# ArduinoProMiniShematic.net
KiCad netlist of a schematic drawn in Altium Designer
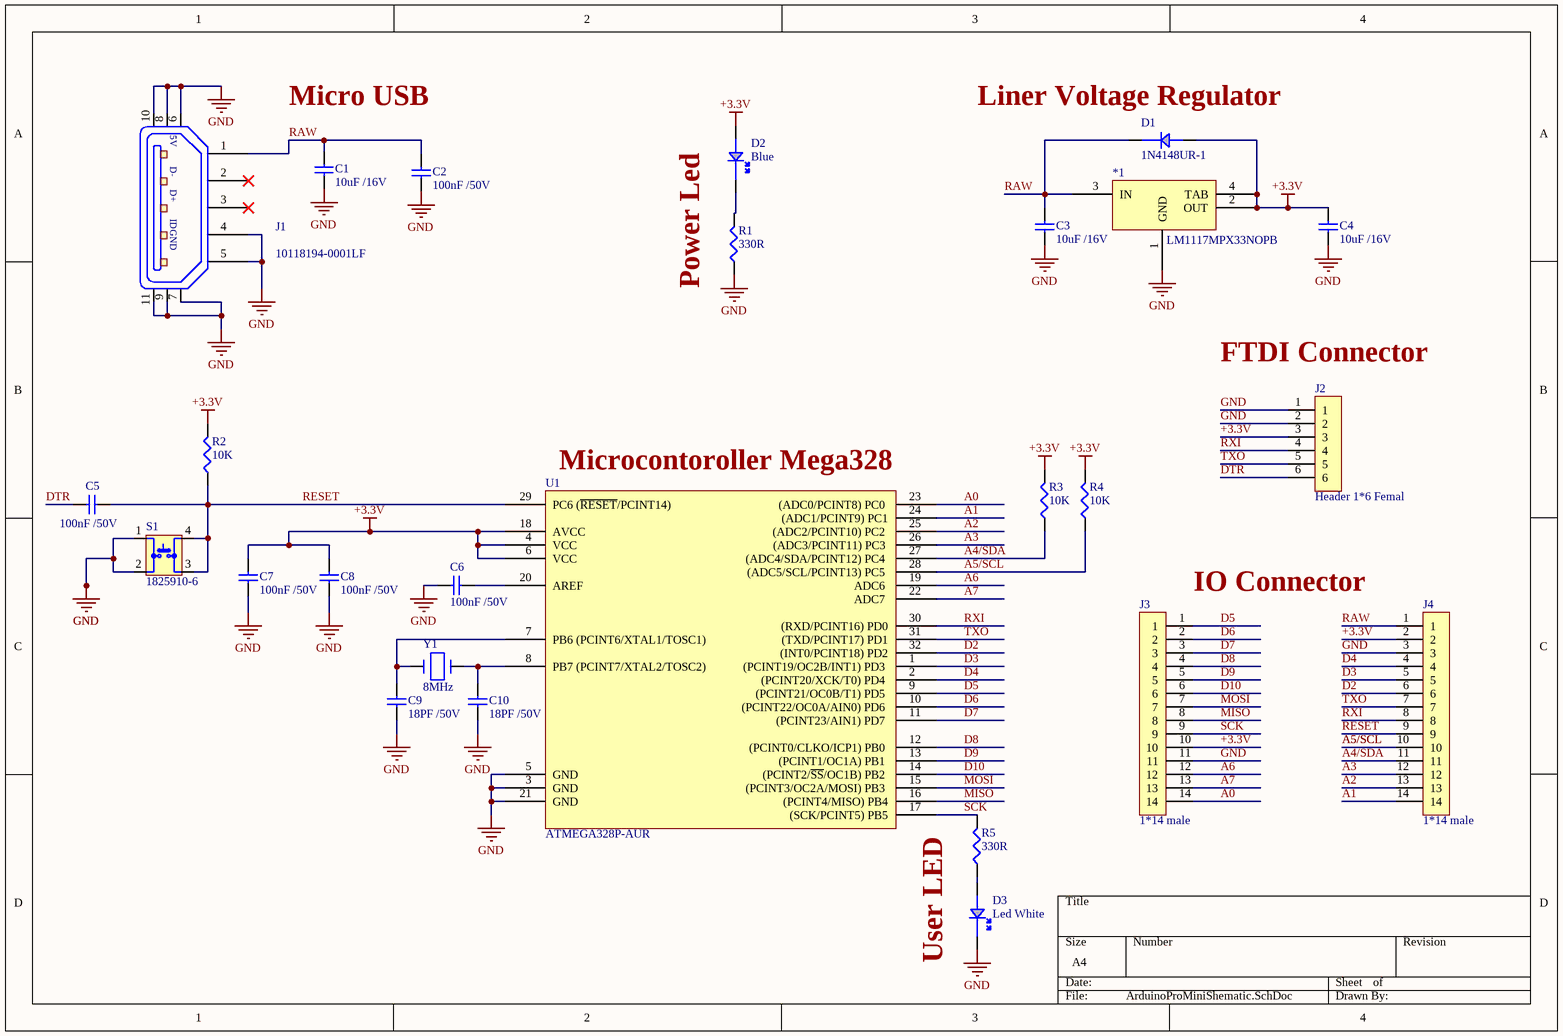
[diagram p0: ArduinoProMiniShematic.SchDoc]

(export (version "E")
  (design (tool "Eeschema 10.0.6"))
  (components
    (comp (ref "*1")
      (value "LM1117MPX33NOPB")
      (footprint "SOT 223")
      (description "IC REG LIN 3.3V 800MA SOT223-4")
      (libsource (lib "ArduinoProMiniSchlib") (part "LM1117MPX33NOPB"))
    )
    (comp (ref "C1")
      (value "10uF /16V")
      (footprint "C 0805")
      (description "KEMET - C0805C106K4PACTU - CERAMIC CAPACITOR, 10UF, 16V, X5R, 10%, 0805")
      (fields (field (name "TOLERANCE") "10%") (field (name "VOLTAGE") "16V"))
      (libsource (lib "ArduinoProMiniSchlib") (part "C0805C106K4PACTU"))
    )
    (comp (ref "C2")
      (value "100nF /50V")
      (footprint "C 0805")
      (description "KEMET         C0805C104Z5VACTU.             CERAMIC CAPACITOR, 0.1UF, 50V, Y5V, +80,-20%, 0805")
      (fields (field (name "VOLTAGE") "50V") (field (name "TOLERANCE") "80%"))
      (libsource (lib "ArduinoProMiniSchlib") (part "C0805C104Z5VACTU"))
    )
    (comp (ref "C3")
      (value "10uF /16V")
      (footprint "C 0805")
      (description "KEMET - C0805C106K4PACTU - CERAMIC CAPACITOR, 10UF, 16V, X5R, 10%, 0805")
      (fields (field (name "TOLERANCE") "10%") (field (name "VOLTAGE") "16V"))
      (libsource (lib "ArduinoProMiniSchlib") (part "C0805C106K4PACTU"))
    )
    (comp (ref "C4")
      (value "10uF /16V")
      (footprint "C 0805")
      (description "KEMET - C0805C106K4PACTU - CERAMIC CAPACITOR, 10UF, 16V, X5R, 10%, 0805")
      (fields (field (name "TOLERANCE") "10%") (field (name "VOLTAGE") "16V"))
      (libsource (lib "ArduinoProMiniSchlib") (part "C0805C106K4PACTU"))
    )
    (comp (ref "C5")
      (value "100nF /50V")
      (footprint "C 0805")
      (description "KEMET         C0805C104Z5VACTU.             CERAMIC CAPACITOR, 0.1UF, 50V, Y5V, +80,-20%, 0805")
      (fields (field (name "VOLTAGE") "50V") (field (name "TOLERANCE") "80%"))
      (libsource (lib "ArduinoProMiniSchlib") (part "C0805C104Z5VACTU"))
    )
    (comp (ref "C6")
      (value "100nF /50V")
      (footprint "C 0805")
      (description "KEMET         C0805C104Z5VACTU.             CERAMIC CAPACITOR, 0.1UF, 50V, Y5V, +80,-20%, 0805")
      (fields (field (name "VOLTAGE") "50V") (field (name "TOLERANCE") "80%"))
      (libsource (lib "ArduinoProMiniSchlib") (part "C0805C104Z5VACTU"))
    )
    (comp (ref "C7")
      (value "100nF /50V")
      (footprint "C 0805")
      (description "KEMET         C0805C104Z5VACTU.             CERAMIC CAPACITOR, 0.1UF, 50V, Y5V, +80,-20%, 0805")
      (fields (field (name "VOLTAGE") "50V") (field (name "TOLERANCE") "80%"))
      (libsource (lib "ArduinoProMiniSchlib") (part "C0805C104Z5VACTU"))
    )
    (comp (ref "C8")
      (value "100nF /50V")
      (footprint "C 0805")
      (description "KEMET         C0805C104Z5VACTU.             CERAMIC CAPACITOR, 0.1UF, 50V, Y5V, +80,-20%, 0805")
      (fields (field (name "VOLTAGE") "50V") (field (name "TOLERANCE") "80%"))
      (libsource (lib "ArduinoProMiniSchlib") (part "C0805C104Z5VACTU"))
    )
    (comp (ref "C9")
      (value "18PF /50V")
      (footprint "C 0805")
      (description "Surface Mount Ceramic Multilayer Capacitor 18pF 5% C0G 50V 0805 Paper T/R")
      (fields (field (name "TOLERANCE") "5%"))
      (libsource (lib "ArduinoProMiniSchlib") (part "CC0805JRNPO9BN180"))
    )
    (comp (ref "C10")
      (value "18PF /50V")
      (footprint "C 0805")
      (description "Surface Mount Ceramic Multilayer Capacitor 18pF 5% C0G 50V 0805 Paper T/R")
      (fields (field (name "TOLERANCE") "5%"))
      (libsource (lib "ArduinoProMiniSchlib") (part "CC0805JRNPO9BN180"))
    )
    (comp (ref "D1")
      (value "1N4148UR-1")
      (footprint "DO 213AA")
      (description "Diode Switching 75V 0.2A 2-Pin DO-213AA")
      (libsource (lib "ArduinoProMiniSchlib") (part "1N4148UR-1"))
    )
    (comp (ref "D2")
      (value "Blue")
      (footprint "LED 0603")
      (description "LED BLUE CLEAR SMD")
      (libsource (lib "ArduinoProMiniSchlib") (part "LTST-C194TBKT"))
    )
    (comp (ref "D3")
      (value "Led White")
      (footprint "LED 0603")
      (description "Led White Clear 0603 SMD")
      (libsource (lib "ArduinoProMiniSchlib") (part "IN-S63AT5UW"))
    )
    (comp (ref "J1")
      (value "10118194-0001LF")
      (footprint "10118194-0001LF")
      (description "CONN USB MICRO B RECPT SMT R/A")
      (libsource (lib "ArduinoProMiniSchlib") (part "10118194-0001LF"))
    )
    (comp (ref "J2")
      (value "Header 1*6 Femal")
      (footprint "Header female 1*6")
      (description "06-WAY SIL VERT SOCKET L/FREE")
      (libsource (lib "ArduinoProMiniSchlib") (part "M20-7820646"))
    )
    (comp (ref "J3")
      (value "1*14 male")
      (footprint "1*4 male header")
      (description "14 Position Single Row Straight Gold Flash Header")
      (libsource (lib "ArduinoProMiniSchlib") (part "PH1-14-UA"))
    )
    (comp (ref "J4")
      (value "1*14 male")
      (footprint "1*4 male header")
      (description "14 Position Single Row Straight Gold Flash Header")
      (libsource (lib "") (part "PH1-14-UA_1"))
    )
    (comp (ref "R1")
      (value "330R")
      (footprint "R 0805")
      (description "YAGEO   RC0805JR-07330RL   THICK FILM RESISTOR, 330 OHM, 125mW, 5%, FULL REEL")
      (fields (field (name "TOLERANCE") "5%"))
      (libsource (lib "ArduinoProMiniSchlib") (part "RC0805JR-07330RL"))
    )
    (comp (ref "R2")
      (value "10K")
      (description "RES SMD 10K OHM 1% 1/8W 0805")
      (fields (field (name "TOLERANCE") "1%"))
      (libsource (lib "ArduinoProMiniSchlib") (part "RC0805FR-0710KL"))
    )
    (comp (ref "R3")
      (value "10K")
      (description "RES SMD 10K OHM 1% 1/8W 0805")
      (fields (field (name "TOLERANCE") "1%"))
      (libsource (lib "ArduinoProMiniSchlib") (part "RC0805FR-0710KL"))
    )
    (comp (ref "R4")
      (value "10K")
      (description "RES SMD 10K OHM 1% 1/8W 0805")
      (fields (field (name "TOLERANCE") "1%"))
      (libsource (lib "ArduinoProMiniSchlib") (part "RC0805FR-0710KL"))
    )
    (comp (ref "R5")
      (value "330R")
      (footprint "R 0805")
      (description "YAGEO   RC0805JR-07330RL   THICK FILM RESISTOR, 330 OHM, 125mW, 5%, FULL REEL")
      (fields (field (name "TOLERANCE") "5%"))
      (libsource (lib "ArduinoProMiniSchlib") (part "RC0805JR-07330RL"))
    )
    (comp (ref "S1")
      (value "1825910-6")
      (footprint "1825910-6")
      (description "SWITCH TACTILE SPST-NO 0.05A 24V")
      (libsource (lib "ArduinoProMiniSchlib") (part "1825910-6"))
    )
    (comp (ref "U1")
      (value "ATMEGA328P-AUR")
      (footprint "TQFP-32")
      (libsource (lib "ArduinoProMiniSchlib") (part "ATMEGA328P-AUR"))
    )
    (comp (ref "Y1")
      (value "8MHz")
      (footprint "CSM-7X")
      (description "Crystal 8MHz ±30ppm (Tol) ±50ppm (Stability) 18pF FUND 60Ohm 2-Pin HC-49/USX SMD T/R")
      (fields (field (name "TOLERANCE") "30ppm"))
      (libsource (lib "ArduinoProMiniSchlib") (part "ECS-80-18-5PX-TR"))
    )
  )
  (nets
    (net (code "1") (name "+3.3V") (class "Default")
      (node (ref "*1") (pin "2") (pinfunction "OUT_2") (pintype "passive"))
      (node (ref "*1") (pin "4") (pinfunction "TAB_4") (pintype "passive"))
      (node (ref "C4") (pin "2") (pinfunction "2_2") (pintype "passive"))
      (node (ref "C7") (pin "2") (pinfunction "2_2") (pintype "passive"))
      (node (ref "C8") (pin "2") (pinfunction "2_2") (pintype "passive"))
      (node (ref "D1") (pin "1") (pinfunction "anode_1") (pintype "passive"))
      (node (ref "D2") (pin "1") (pinfunction "anode_1") (pintype "passive"))
      (node (ref "J2") (pin "3") (pinfunction "3_3") (pintype "passive"))
      (node (ref "J3") (pin "10") (pinfunction "10_10") (pintype "passive"))
      (node (ref "J4") (pin "2") (pinfunction "2_2") (pintype "passive"))
      (node (ref "R2") (pin "6") (pinfunction "6_6") (pintype "passive"))
      (node (ref "R3") (pin "6") (pinfunction "6_6") (pintype "passive"))
      (node (ref "R4") (pin "6") (pinfunction "6_6") (pintype "passive"))
      (node (ref "U1") (pin "18") (pinfunction "AVCC_18") (pintype "passive"))
      (node (ref "U1") (pin "4") (pinfunction "VCC_4") (pintype "passive"))
      (node (ref "U1") (pin "6") (pinfunction "VCC_6") (pintype "passive"))
    )
    (net (code "2") (name "/A0") (class "Default")
      (node (ref "J3") (pin "14") (pinfunction "14_14") (pintype "passive"))
      (node (ref "U1") (pin "23") (pinfunction "(ADC0/PCINT8)_PC0_23") (pintype "passive"))
    )
    (net (code "3") (name "/A1") (class "Default")
      (node (ref "J4") (pin "14") (pinfunction "14_14") (pintype "passive"))
      (node (ref "U1") (pin "24") (pinfunction "(ADC1/PCINT9)_PC1_24") (pintype "passive"))
    )
    (net (code "4") (name "/A2") (class "Default")
      (node (ref "J4") (pin "13") (pinfunction "13_13") (pintype "passive"))
      (node (ref "U1") (pin "25") (pinfunction "(ADC2/PCINT10)_PC2_25") (pintype "passive"))
    )
    (net (code "5") (name "/A3") (class "Default")
      (node (ref "J4") (pin "12") (pinfunction "12_12") (pintype "passive"))
      (node (ref "U1") (pin "26") (pinfunction "(ADC3/PCINT11)_PC3_26") (pintype "passive"))
    )
    (net (code "6") (name "/A4{slash}SDA") (class "Default")
      (node (ref "J4") (pin "11") (pinfunction "11_11") (pintype "passive"))
      (node (ref "R3") (pin "5") (pinfunction "5_5") (pintype "passive"))
      (node (ref "U1") (pin "27") (pinfunction "(ADC4/SDA/PCINT12)_PC4_27") (pintype "passive"))
    )
    (net (code "7") (name "/A5{slash}SCL") (class "Default")
      (node (ref "J4") (pin "10") (pinfunction "10_10") (pintype "passive"))
      (node (ref "R4") (pin "5") (pinfunction "5_5") (pintype "passive"))
      (node (ref "U1") (pin "28") (pinfunction "(ADC5/SCL/PCINT13)_PC5_28") (pintype "passive"))
    )
    (net (code "8") (name "/A6") (class "Default")
      (node (ref "J3") (pin "12") (pinfunction "12_12") (pintype "passive"))
      (node (ref "U1") (pin "19") (pinfunction "ADC6_19") (pintype "passive"))
    )
    (net (code "9") (name "/A7") (class "Default")
      (node (ref "J3") (pin "13") (pinfunction "13_13") (pintype "passive"))
      (node (ref "U1") (pin "22") (pinfunction "ADC7_22") (pintype "passive"))
    )
    (net (code "10") (name "/D2") (class "Default")
      (node (ref "J4") (pin "6") (pinfunction "6_6") (pintype "passive"))
      (node (ref "U1") (pin "32") (pinfunction "(INT0/PCINT18)_PD2_32") (pintype "passive"))
    )
    (net (code "11") (name "/D3") (class "Default")
      (node (ref "J4") (pin "5") (pinfunction "5_5") (pintype "passive"))
      (node (ref "U1") (pin "1") (pinfunction "(PCINT19/OC2B/INT1)_PD3_1") (pintype "passive"))
    )
    (net (code "12") (name "/D4") (class "Default")
      (node (ref "J4") (pin "4") (pinfunction "4_4") (pintype "passive"))
      (node (ref "U1") (pin "2") (pinfunction "(PCINT20/XCK/T0)_PD4_2") (pintype "passive"))
    )
    (net (code "13") (name "/D5") (class "Default")
      (node (ref "J3") (pin "1") (pinfunction "1_1") (pintype "passive"))
      (node (ref "U1") (pin "9") (pinfunction "(PCINT21/OC0B/T1)_PD5_9") (pintype "passive"))
    )
    (net (code "14") (name "/D6") (class "Default")
      (node (ref "J3") (pin "2") (pinfunction "2_2") (pintype "passive"))
      (node (ref "U1") (pin "10") (pinfunction "(PCINT22/OC0A/AIN0)_PD6_10") (pintype "passive"))
    )
    (net (code "15") (name "/D7") (class "Default")
      (node (ref "J3") (pin "3") (pinfunction "3_3") (pintype "passive"))
      (node (ref "U1") (pin "11") (pinfunction "(PCINT23/AIN1)_PD7_11") (pintype "passive"))
    )
    (net (code "16") (name "/D8") (class "Default")
      (node (ref "J3") (pin "4") (pinfunction "4_4") (pintype "passive"))
      (node (ref "U1") (pin "12") (pinfunction "(PCINT0/CLKO/ICP1)_PB0_12") (pintype "passive"))
    )
    (net (code "17") (name "/D9") (class "Default")
      (node (ref "J3") (pin "5") (pinfunction "5_5") (pintype "passive"))
      (node (ref "U1") (pin "13") (pinfunction "(PCINT1/OC1A)_PB1_13") (pintype "passive"))
    )
    (net (code "18") (name "/D10") (class "Default")
      (node (ref "J3") (pin "6") (pinfunction "6_6") (pintype "passive"))
      (node (ref "U1") (pin "14") (pinfunction "(PCINT2/~{SS}/OC1B)_PB2_14") (pintype "passive"))
    )
    (net (code "19") (name "/DTR") (class "Default")
      (node (ref "C5") (pin "1") (pinfunction "1_1") (pintype "passive"))
      (node (ref "J2") (pin "6") (pinfunction "6_6") (pintype "passive"))
    )
    (net (code "20") (name "/MISO") (class "Default")
      (node (ref "J3") (pin "8") (pinfunction "8_8") (pintype "passive"))
      (node (ref "U1") (pin "16") (pinfunction "(PCINT4/MISO)_PB4_16") (pintype "passive"))
    )
    (net (code "21") (name "/MOSI") (class "Default")
      (node (ref "J3") (pin "7") (pinfunction "7_7") (pintype "passive"))
      (node (ref "U1") (pin "15") (pinfunction "(PCINT3/OC2A/MOSI)_PB3_15") (pintype "passive"))
    )
    (net (code "22") (name "/RAW") (class "Default")
      (node (ref "*1") (pin "3") (pinfunction "IN_3") (pintype "passive"))
      (node (ref "C1") (pin "2") (pinfunction "2_2") (pintype "passive"))
      (node (ref "C2") (pin "1") (pinfunction "1_1") (pintype "passive"))
      (node (ref "C3") (pin "2") (pinfunction "2_2") (pintype "passive"))
      (node (ref "D1") (pin "2") (pinfunction "cathode_2") (pintype "passive"))
      (node (ref "J1") (pin "1") (pinfunction "1_1") (pintype "passive"))
      (node (ref "J4") (pin "1") (pinfunction "1_1") (pintype "passive"))
    )
    (net (code "23") (name "/RESET") (class "Default")
      (node (ref "C5") (pin "2") (pinfunction "2_2") (pintype "passive"))
      (node (ref "J4") (pin "9") (pinfunction "9_9") (pintype "passive"))
      (node (ref "R2") (pin "5") (pinfunction "5_5") (pintype "passive"))
      (node (ref "S1") (pin "3") (pinfunction "3_3") (pintype "passive"))
      (node (ref "S1") (pin "4") (pinfunction "4_4") (pintype "passive"))
      (node (ref "U1") (pin "29") (pinfunction "PC6_(~{RESET}/PCINT14)_29") (pintype "passive"))
    )
    (net (code "24") (name "/RXI") (class "Default")
      (node (ref "J2") (pin "4") (pinfunction "4_4") (pintype "passive"))
      (node (ref "J4") (pin "8") (pinfunction "8_8") (pintype "passive"))
      (node (ref "U1") (pin "30") (pinfunction "(RXD/PCINT16)_PD0_30") (pintype "passive"))
    )
    (net (code "25") (name "/SCK") (class "Default")
      (node (ref "J3") (pin "9") (pinfunction "9_9") (pintype "passive"))
      (node (ref "R5") (pin "6") (pinfunction "6_6") (pintype "passive"))
      (node (ref "U1") (pin "17") (pinfunction "(SCK/PCINT5)_PB5_17") (pintype "passive"))
    )
    (net (code "26") (name "/TXO") (class "Default")
      (node (ref "J2") (pin "5") (pinfunction "5_5") (pintype "passive"))
      (node (ref "J4") (pin "7") (pinfunction "7_7") (pintype "passive"))
      (node (ref "U1") (pin "31") (pinfunction "(TXD/PCINT17)_PD1_31") (pintype "passive"))
    )
    (net (code "27") (name "GND") (class "Default")
      (node (ref "*1") (pin "1") (pinfunction "GND_1") (pintype "passive"))
      (node (ref "C1") (pin "1") (pinfunction "1_1") (pintype "passive"))
      (node (ref "C10") (pin "1") (pinfunction "1_1") (pintype "passive"))
      (node (ref "C2") (pin "2") (pinfunction "2_2") (pintype "passive"))
      (node (ref "C3") (pin "1") (pinfunction "1_1") (pintype "passive"))
      (node (ref "C4") (pin "1") (pinfunction "1_1") (pintype "passive"))
      (node (ref "C6") (pin "2") (pinfunction "2_2") (pintype "passive"))
      (node (ref "C7") (pin "1") (pinfunction "1_1") (pintype "passive"))
      (node (ref "C8") (pin "1") (pinfunction "1_1") (pintype "passive"))
      (node (ref "C9") (pin "1") (pinfunction "1_1") (pintype "passive"))
      (node (ref "D3") (pin "2") (pinfunction "cathode_2") (pintype "passive"))
      (node (ref "J1") (pin "10") (pinfunction "10_10") (pintype "passive"))
      (node (ref "J1") (pin "11") (pinfunction "11_11") (pintype "passive"))
      (node (ref "J1") (pin "4") (pinfunction "4_4") (pintype "passive"))
      (node (ref "J1") (pin "5") (pinfunction "5_5") (pintype "passive"))
      (node (ref "J1") (pin "6") (pinfunction "6_6") (pintype "passive"))
      (node (ref "J1") (pin "7") (pinfunction "7_7") (pintype "passive"))
      (node (ref "J1") (pin "8") (pinfunction "8_8") (pintype "passive"))
      (node (ref "J1") (pin "9") (pinfunction "9_9") (pintype "passive"))
      (node (ref "J2") (pin "1") (pinfunction "1_1") (pintype "passive"))
      (node (ref "J2") (pin "2") (pinfunction "2_2") (pintype "passive"))
      (node (ref "J3") (pin "11") (pinfunction "11_11") (pintype "passive"))
      (node (ref "J4") (pin "3") (pinfunction "3_3") (pintype "passive"))
      (node (ref "R1") (pin "5") (pinfunction "5_5") (pintype "passive"))
      (node (ref "S1") (pin "1") (pinfunction "1_1") (pintype "passive"))
      (node (ref "S1") (pin "2") (pinfunction "2_2") (pintype "passive"))
      (node (ref "U1") (pin "21") (pinfunction "GND_21") (pintype "passive"))
      (node (ref "U1") (pin "3") (pinfunction "GND_3") (pintype "passive"))
      (node (ref "U1") (pin "5") (pinfunction "GND_5") (pintype "passive"))
    )
    (net (code "28") (name "Net-(D2-cathode)") (class "Default")
      (node (ref "D2") (pin "2") (pinfunction "cathode_2") (pintype "passive"))
      (node (ref "R1") (pin "6") (pinfunction "6_6") (pintype "passive"))
    )
    (net (code "29") (name "Net-(D3-anode)") (class "Default")
      (node (ref "D3") (pin "1") (pinfunction "anode_1") (pintype "passive"))
      (node (ref "R5") (pin "5") (pinfunction "5_5") (pintype "passive"))
    )
    (net (code "30") (name "Net-(U1-AREF)") (class "Default")
      (node (ref "C6") (pin "1") (pinfunction "1_1") (pintype "passive"))
      (node (ref "U1") (pin "20") (pinfunction "AREF_20") (pintype "passive"))
    )
    (net (code "31") (name "Net-(U1-PB6_(PCINT6{slash}XTAL1{slash}TOSC1))") (class "Default")
      (node (ref "C9") (pin "2") (pinfunction "2_2") (pintype "passive"))
      (node (ref "U1") (pin "7") (pinfunction "PB6_(PCINT6/XTAL1/TOSC1)_7") (pintype "passive"))
      (node (ref "Y1") (pin "1") (pintype "passive"))
    )
    (net (code "32") (name "Net-(U1-PB7_(PCINT7{slash}XTAL2{slash}TOSC2))") (class "Default")
      (node (ref "C10") (pin "2") (pinfunction "2_2") (pintype "passive"))
      (node (ref "U1") (pin "8") (pinfunction "PB7_(PCINT7/XTAL2/TOSC2)_8") (pintype "passive"))
      (node (ref "Y1") (pin "2") (pintype "passive"))
    )
    (net (code "33") (name "unconnected-(J1-Pad2)") (class "Default")
      (node (ref "J1") (pin "2") (pinfunction "2_2") (pintype "passive+no_connect"))
    )
    (net (code "34") (name "unconnected-(J1-Pad3)") (class "Default")
      (node (ref "J1") (pin "3") (pinfunction "3_3") (pintype "passive+no_connect"))
    )
  )
)
